# schemate.net
KiCad netlist of a schematic drawn in EAGLE
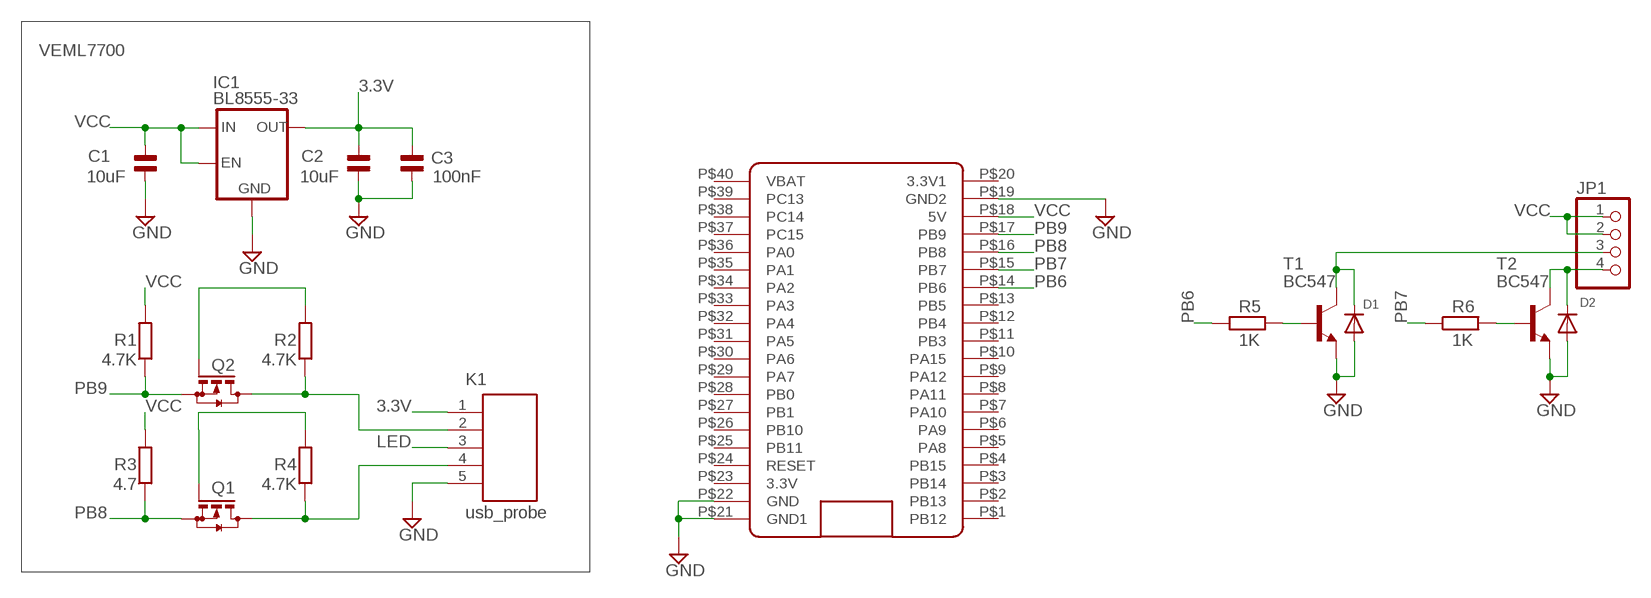
[diagram p0: schematic, sheet 1]

(export (version "E")
  (design (tool "Eeschema 10.0.6"))
  (components
    (comp (ref "C1")
      (value "10uF")
      (footprint "eagle-import:C-0805")
      (libsource (lib "eagle-import") (part "C-NP-SMD-0805"))
    )
    (comp (ref "C2")
      (value "10uF")
      (footprint "eagle-import:C-0805")
      (libsource (lib "eagle-import") (part "C-NP-SMD-0805"))
    )
    (comp (ref "C3")
      (value "100nF")
      (footprint "eagle-import:C-0805")
      (libsource (lib "eagle-import") (part "C-NP-SMD-0805"))
    )
    (comp (ref "D1")
      (value "DIODESOD-123")
      (footprint "eagle-import:SOD-123")
      (libsource (lib "eagle-import") (part "DIODESOD-123"))
    )
    (comp (ref "D2")
      (value "DIODESOD-123")
      (footprint "eagle-import:SOD-123")
      (libsource (lib "eagle-import") (part "DIODESOD-123"))
    )
    (comp (ref "IC1")
      (value "BL8555-33")
      (footprint "eagle-import:SOT23-5")
      (fields (field (name "MF") "Texas Instruments") (field (name "MPN") "TPS70928DBVT"))
      (libsource (lib "eagle-import") (part "TPS709DBV28"))
    )
    (comp (ref "JP1")
      (value "PINHD-1X4")
      (footprint "eagle-import:1X04")
      (libsource (lib "eagle-import") (part "PINHD-1X4"))
    )
    (comp (ref "K1")
      (value "usb_probe")
      (footprint "eagle-import:629105136821")
      (libsource (lib "eagle-import") (part "629105136821"))
    )
    (comp (ref "Q1")
      (value "BSS123")
      (footprint "eagle-import:SOT23")
      (libsource (lib "eagle-import") (part "BSS123"))
    )
    (comp (ref "Q2")
      (value "BSS123")
      (footprint "eagle-import:SOT23")
      (libsource (lib "eagle-import") (part "BSS123"))
    )
    (comp (ref "R1")
      (value "4.7K")
      (footprint "eagle-import:M0805")
      (libsource (lib "eagle-import") (part "resistor_348_R-EU_M0805"))
    )
    (comp (ref "R2")
      (value "4.7K")
      (footprint "eagle-import:M0805")
      (libsource (lib "eagle-import") (part "resistor_348_R-EU_M0805"))
    )
    (comp (ref "R3")
      (value "4.7")
      (footprint "eagle-import:M0805")
      (libsource (lib "eagle-import") (part "resistor_348_R-EU_M0805"))
    )
    (comp (ref "R4")
      (value "4.7K")
      (footprint "eagle-import:M0805")
      (libsource (lib "eagle-import") (part "resistor_348_R-EU_M0805"))
    )
    (comp (ref "R5")
      (value "1K")
      (footprint "eagle-import:0204_7")
      (libsource (lib "eagle-import") (part "R-EU_0204/7"))
    )
    (comp (ref "R6")
      (value "1K")
      (footprint "eagle-import:0204_7")
      (libsource (lib "eagle-import") (part "R-EU_0204/7"))
    )
    (comp (ref "T1")
      (value "BC547")
      (footprint "eagle-import:TO92")
      (libsource (lib "eagle-import") (part "BC547"))
    )
    (comp (ref "T2")
      (value "BC547")
      (footprint "eagle-import:TO92")
      (libsource (lib "eagle-import") (part "BC547"))
    )
    (comp (ref "U$1")
      (value "BLUE_PILL")
      (footprint "eagle-import:BLUE_PILL")
      (libsource (lib "eagle-import") (part "BLUE_PILL"))
    )
  )
  (nets
    (net (code "1") (name "/3.3V") (class "Default")
      (node (ref "C2") (pin "2") (pinfunction "2_2") (pintype "passive"))
      (node (ref "C3") (pin "2") (pinfunction "2_2") (pintype "passive"))
      (node (ref "IC1") (pin "5") (pinfunction "OUT_5") (pintype "passive"))
      (node (ref "K1") (pin "1") (pinfunction "1_1") (pintype "passive"))
      (node (ref "K1") (pin "2") (pinfunction "2_2") (pintype "passive"))
      (node (ref "Q2") (pin "3") (pinfunction "D_3") (pintype "passive"))
      (node (ref "R2") (pin "1") (pinfunction "1_1") (pintype "passive"))
    )
    (net (code "2") (name "/LED") (class "Default")
      (node (ref "K1") (pin "3") (pinfunction "3_3") (pintype "passive"))
    )
    (net (code "3") (name "/PB6") (class "Default")
      (node (ref "R5") (pin "1") (pinfunction "1_1") (pintype "passive"))
      (node (ref "U$1") (pin "P$14") (pinfunction "PB6_P$14") (pintype "bidirectional"))
    )
    (net (code "4") (name "/PB7") (class "Default")
      (node (ref "R6") (pin "1") (pinfunction "1_1") (pintype "passive"))
      (node (ref "U$1") (pin "P$15") (pinfunction "PB7_P$15") (pintype "bidirectional"))
    )
    (net (code "5") (name "/PB8") (class "Default")
      (node (ref "Q1") (pin "2") (pinfunction "S_2") (pintype "passive"))
      (node (ref "R3") (pin "1") (pinfunction "1_1") (pintype "passive"))
      (node (ref "U$1") (pin "P$16") (pinfunction "PB8_P$16") (pintype "bidirectional"))
    )
    (net (code "6") (name "/PB9") (class "Default")
      (node (ref "Q2") (pin "2") (pinfunction "S_2") (pintype "passive"))
      (node (ref "R1") (pin "1") (pinfunction "1_1") (pintype "passive"))
      (node (ref "U$1") (pin "P$17") (pinfunction "PB9_P$17") (pintype "bidirectional"))
    )
    (net (code "7") (name "/VCC") (class "Default")
      (node (ref "C1") (pin "2") (pinfunction "2_2") (pintype "passive"))
      (node (ref "IC1") (pin "1") (pinfunction "IN_1") (pintype "input"))
      (node (ref "IC1") (pin "3") (pinfunction "EN_3") (pintype "input"))
      (node (ref "JP1") (pin "1") (pinfunction "1_1") (pintype "passive"))
      (node (ref "JP1") (pin "2") (pinfunction "2_2") (pintype "passive"))
      (node (ref "R1") (pin "2") (pinfunction "2_2") (pintype "passive"))
      (node (ref "R3") (pin "2") (pinfunction "2_2") (pintype "passive"))
      (node (ref "U$1") (pin "P$18") (pinfunction "5V_P$18") (pintype "bidirectional"))
    )
    (net (code "8") (name "GND") (class "Default")
      (node (ref "C1") (pin "1") (pinfunction "1_1") (pintype "passive"))
      (node (ref "C2") (pin "1") (pinfunction "1_1") (pintype "passive"))
      (node (ref "C3") (pin "1") (pinfunction "1_1") (pintype "passive"))
      (node (ref "D1") (pin "A") (pinfunction "A_A") (pintype "passive"))
      (node (ref "D2") (pin "A") (pinfunction "A_A") (pintype "passive"))
      (node (ref "IC1") (pin "2") (pinfunction "GND_2") (pintype "input"))
      (node (ref "K1") (pin "5") (pinfunction "5_5") (pintype "passive"))
      (node (ref "T1") (pin "1") (pinfunction "E_1") (pintype "passive"))
      (node (ref "T2") (pin "1") (pinfunction "E_1") (pintype "passive"))
      (node (ref "U$1") (pin "P$19") (pinfunction "GND2_P$19") (pintype "bidirectional"))
      (node (ref "U$1") (pin "P$21") (pinfunction "GND1_P$21") (pintype "power_in"))
      (node (ref "U$1") (pin "P$22") (pinfunction "GND_P$22") (pintype "bidirectional"))
    )
    (net (code "9") (name "Net-(Q1-D)") (class "Default")
      (node (ref "K1") (pin "4") (pinfunction "4_4") (pintype "passive"))
      (node (ref "Q1") (pin "3") (pinfunction "D_3") (pintype "passive"))
      (node (ref "R4") (pin "1") (pinfunction "1_1") (pintype "passive"))
    )
    (net (code "10") (name "Net-(Q1-G)") (class "Default")
      (node (ref "Q1") (pin "1") (pinfunction "G_1") (pintype "passive"))
      (node (ref "R4") (pin "2") (pinfunction "2_2") (pintype "passive"))
    )
    (net (code "11") (name "Net-(Q2-G)") (class "Default")
      (node (ref "Q2") (pin "1") (pinfunction "G_1") (pintype "passive"))
      (node (ref "R2") (pin "2") (pinfunction "2_2") (pintype "passive"))
    )
    (net (code "12") (name "Net-(T1-B)") (class "Default")
      (node (ref "R5") (pin "2") (pinfunction "2_2") (pintype "passive"))
      (node (ref "T1") (pin "2") (pinfunction "B_2") (pintype "passive"))
    )
    (net (code "13") (name "Net-(T1-C)") (class "Default")
      (node (ref "D1") (pin "C") (pinfunction "C_C") (pintype "passive"))
      (node (ref "JP1") (pin "3") (pinfunction "3_3") (pintype "passive"))
      (node (ref "T1") (pin "3") (pinfunction "C_3") (pintype "passive"))
    )
    (net (code "14") (name "Net-(T2-B)") (class "Default")
      (node (ref "R6") (pin "2") (pinfunction "2_2") (pintype "passive"))
      (node (ref "T2") (pin "2") (pinfunction "B_2") (pintype "passive"))
    )
    (net (code "15") (name "Net-(T2-C)") (class "Default")
      (node (ref "D2") (pin "C") (pinfunction "C_C") (pintype "passive"))
      (node (ref "JP1") (pin "4") (pinfunction "4_4") (pintype "passive"))
      (node (ref "T2") (pin "3") (pinfunction "C_3") (pintype "passive"))
    )
    (net (code "16") (name "unconnected-(U$1-3.3V-PadP$23)") (class "Default")
      (node (ref "U$1") (pin "P$23") (pinfunction "3.3V_P$23") (pintype "bidirectional"))
    )
    (net (code "17") (name "unconnected-(U$1-3.3V1-PadP$20)") (class "Default")
      (node (ref "U$1") (pin "P$20") (pinfunction "3.3V1_P$20") (pintype "bidirectional"))
    )
    (net (code "18") (name "unconnected-(U$1-PA0-PadP$36)") (class "Default")
      (node (ref "U$1") (pin "P$36") (pinfunction "PA0_P$36") (pintype "bidirectional"))
    )
    (net (code "19") (name "unconnected-(U$1-PA1-PadP$35)") (class "Default")
      (node (ref "U$1") (pin "P$35") (pinfunction "PA1_P$35") (pintype "bidirectional"))
    )
    (net (code "20") (name "unconnected-(U$1-PA2-PadP$34)") (class "Default")
      (node (ref "U$1") (pin "P$34") (pinfunction "PA2_P$34") (pintype "bidirectional"))
    )
    (net (code "21") (name "unconnected-(U$1-PA3-PadP$33)") (class "Default")
      (node (ref "U$1") (pin "P$33") (pinfunction "PA3_P$33") (pintype "bidirectional"))
    )
    (net (code "22") (name "unconnected-(U$1-PA4-PadP$32)") (class "Default")
      (node (ref "U$1") (pin "P$32") (pinfunction "PA4_P$32") (pintype "bidirectional"))
    )
    (net (code "23") (name "unconnected-(U$1-PA5-PadP$31)") (class "Default")
      (node (ref "U$1") (pin "P$31") (pinfunction "PA5_P$31") (pintype "bidirectional"))
    )
    (net (code "24") (name "unconnected-(U$1-PA6-PadP$30)") (class "Default")
      (node (ref "U$1") (pin "P$30") (pinfunction "PA6_P$30") (pintype "bidirectional"))
    )
    (net (code "25") (name "unconnected-(U$1-PA7-PadP$29)") (class "Default")
      (node (ref "U$1") (pin "P$29") (pinfunction "PA7_P$29") (pintype "bidirectional"))
    )
    (net (code "26") (name "unconnected-(U$1-PA8-PadP$5)") (class "Default")
      (node (ref "U$1") (pin "P$5") (pinfunction "PA8_P$5") (pintype "bidirectional"))
    )
    (net (code "27") (name "unconnected-(U$1-PA9-PadP$6)") (class "Default")
      (node (ref "U$1") (pin "P$6") (pinfunction "PA9_P$6") (pintype "bidirectional"))
    )
    (net (code "28") (name "unconnected-(U$1-PA10-PadP$7)") (class "Default")
      (node (ref "U$1") (pin "P$7") (pinfunction "PA10_P$7") (pintype "bidirectional"))
    )
    (net (code "29") (name "unconnected-(U$1-PA11-PadP$8)") (class "Default")
      (node (ref "U$1") (pin "P$8") (pinfunction "PA11_P$8") (pintype "bidirectional"))
    )
    (net (code "30") (name "unconnected-(U$1-PA12-PadP$9)") (class "Default")
      (node (ref "U$1") (pin "P$9") (pinfunction "PA12_P$9") (pintype "bidirectional"))
    )
    (net (code "31") (name "unconnected-(U$1-PA15-PadP$10)") (class "Default")
      (node (ref "U$1") (pin "P$10") (pinfunction "PA15_P$10") (pintype "bidirectional"))
    )
    (net (code "32") (name "unconnected-(U$1-PB0-PadP$28)") (class "Default")
      (node (ref "U$1") (pin "P$28") (pinfunction "PB0_P$28") (pintype "bidirectional"))
    )
    (net (code "33") (name "unconnected-(U$1-PB1-PadP$27)") (class "Default")
      (node (ref "U$1") (pin "P$27") (pinfunction "PB1_P$27") (pintype "bidirectional"))
    )
    (net (code "34") (name "unconnected-(U$1-PB3-PadP$11)") (class "Default")
      (node (ref "U$1") (pin "P$11") (pinfunction "PB3_P$11") (pintype "bidirectional"))
    )
    (net (code "35") (name "unconnected-(U$1-PB4-PadP$12)") (class "Default")
      (node (ref "U$1") (pin "P$12") (pinfunction "PB4_P$12") (pintype "bidirectional"))
    )
    (net (code "36") (name "unconnected-(U$1-PB5-PadP$13)") (class "Default")
      (node (ref "U$1") (pin "P$13") (pinfunction "PB5_P$13") (pintype "bidirectional"))
    )
    (net (code "37") (name "unconnected-(U$1-PB10-PadP$26)") (class "Default")
      (node (ref "U$1") (pin "P$26") (pinfunction "PB10_P$26") (pintype "bidirectional"))
    )
    (net (code "38") (name "unconnected-(U$1-PB11-PadP$25)") (class "Default")
      (node (ref "U$1") (pin "P$25") (pinfunction "PB11_P$25") (pintype "bidirectional"))
    )
    (net (code "39") (name "unconnected-(U$1-PB12-PadP$1)") (class "Default")
      (node (ref "U$1") (pin "P$1") (pinfunction "PB12_P$1") (pintype "bidirectional"))
    )
    (net (code "40") (name "unconnected-(U$1-PB13-PadP$2)") (class "Default")
      (node (ref "U$1") (pin "P$2") (pinfunction "PB13_P$2") (pintype "bidirectional"))
    )
    (net (code "41") (name "unconnected-(U$1-PB14-PadP$3)") (class "Default")
      (node (ref "U$1") (pin "P$3") (pinfunction "PB14_P$3") (pintype "bidirectional"))
    )
    (net (code "42") (name "unconnected-(U$1-PB15-PadP$4)") (class "Default")
      (node (ref "U$1") (pin "P$4") (pinfunction "PB15_P$4") (pintype "bidirectional"))
    )
    (net (code "43") (name "unconnected-(U$1-PC13-PadP$39)") (class "Default")
      (node (ref "U$1") (pin "P$39") (pinfunction "PC13_P$39") (pintype "bidirectional"))
    )
    (net (code "44") (name "unconnected-(U$1-PC14-PadP$38)") (class "Default")
      (node (ref "U$1") (pin "P$38") (pinfunction "PC14_P$38") (pintype "bidirectional"))
    )
    (net (code "45") (name "unconnected-(U$1-PC15-PadP$37)") (class "Default")
      (node (ref "U$1") (pin "P$37") (pinfunction "PC15_P$37") (pintype "bidirectional"))
    )
    (net (code "46") (name "unconnected-(U$1-RESET-PadP$24)") (class "Default")
      (node (ref "U$1") (pin "P$24") (pinfunction "RESET_P$24") (pintype "bidirectional"))
    )
    (net (code "47") (name "unconnected-(U$1-VBAT-PadP$40)") (class "Default")
      (node (ref "U$1") (pin "P$40") (pinfunction "VBAT_P$40") (pintype "bidirectional"))
    )
  )
)
